# PCB-MicroGPIO.net
KiCad netlist of a schematic drawn in EAGLE
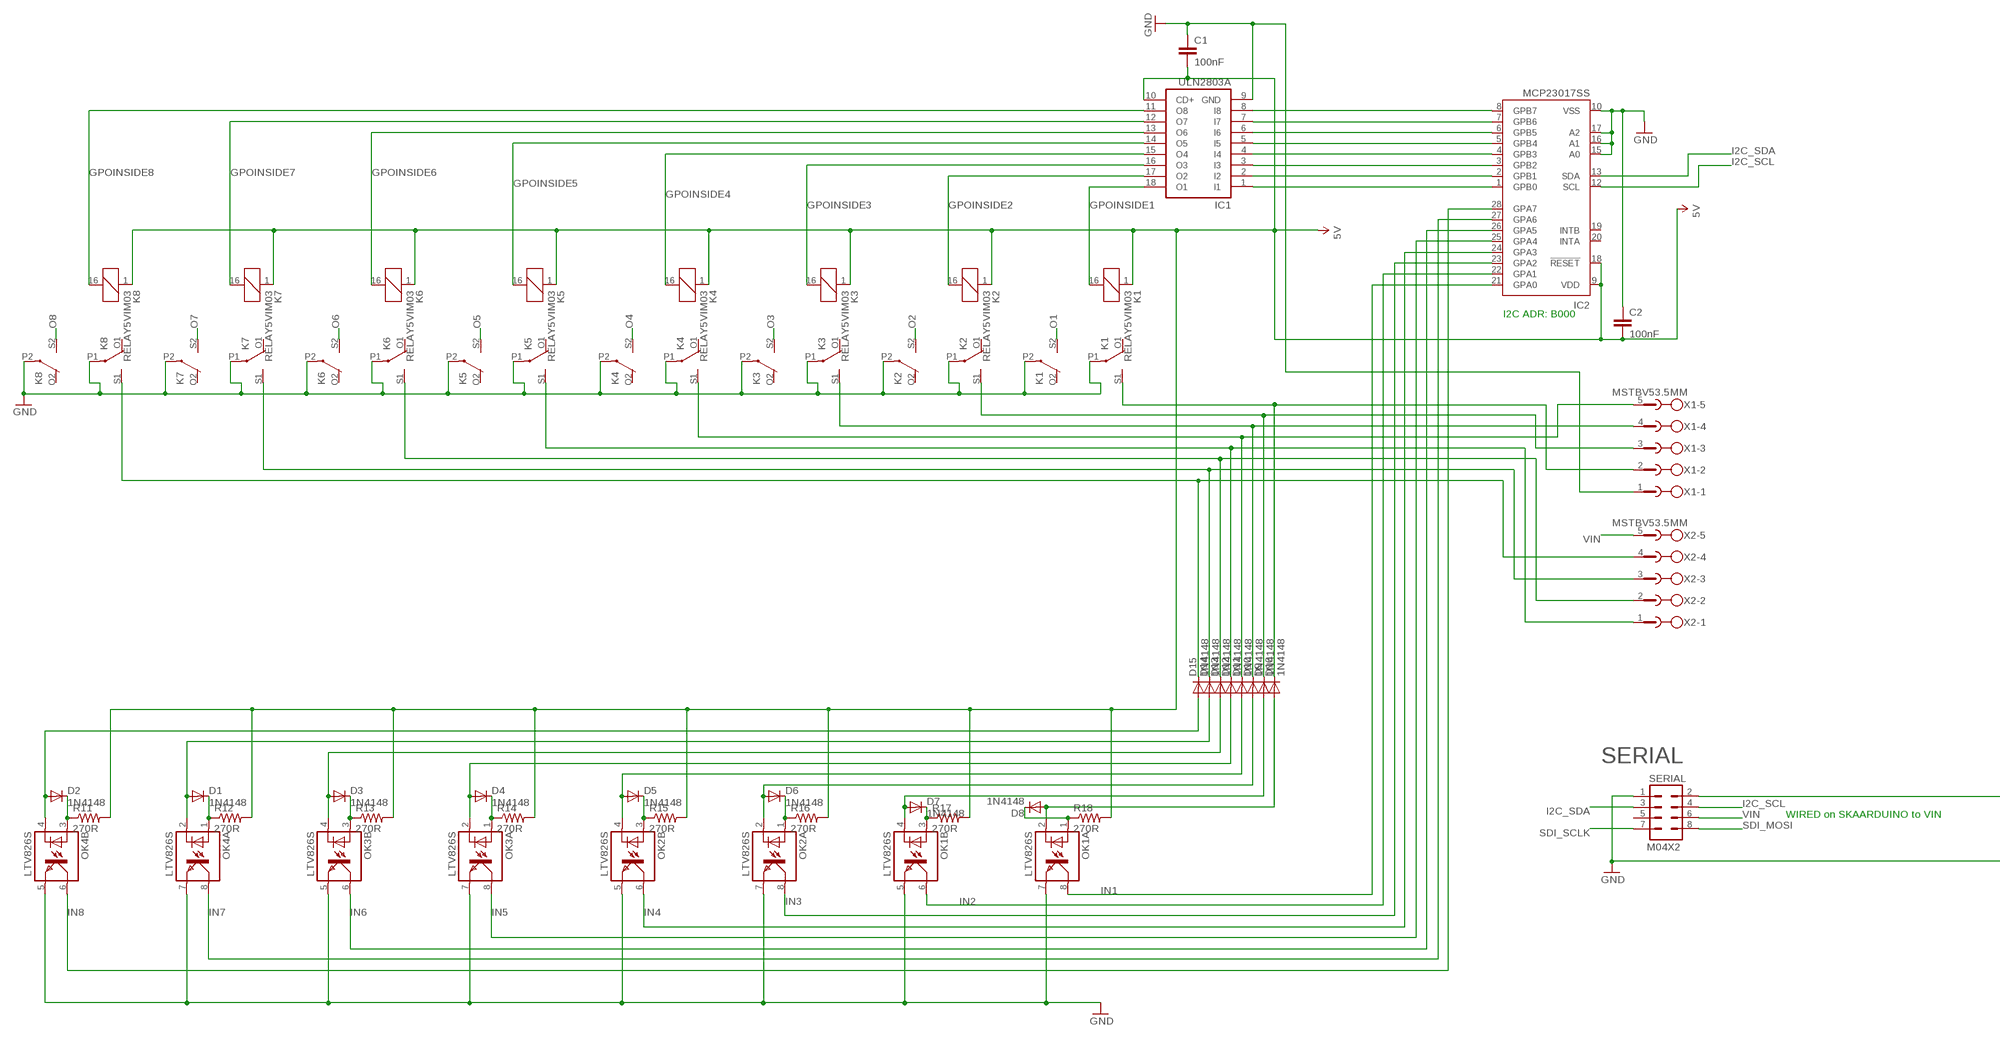
[diagram p0: schematic, sheet 1, part 1 of 2]
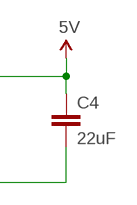
[diagram p1: schematic, sheet 1, part 2 of 2]

(export (version "E")
  (design (tool "Eeschema 10.0.6"))
  (components
    (comp (ref "C1")
      (value "100nF")
      (footprint "eagle-import:0603-CAP")
      (libsource (lib "eagle-import") (part "CAP0603-CAP"))
    )
    (comp (ref "C2")
      (value "100nF")
      (footprint "eagle-import:0603-CAP")
      (libsource (lib "eagle-import") (part "CAP0603-CAP"))
    )
    (comp (ref "C4")
      (value "22uF")
      (footprint "eagle-import:0805")
      (libsource (lib "eagle-import") (part "CAP0805"))
    )
    (comp (ref "D1")
      (value "1N4148")
      (footprint "eagle-import:SOD-323")
      (libsource (lib "eagle-import") (part "DIODESOD"))
    )
    (comp (ref "D2")
      (value "1N4148")
      (footprint "eagle-import:SOD-323")
      (libsource (lib "eagle-import") (part "DIODESOD"))
    )
    (comp (ref "D3")
      (value "1N4148")
      (footprint "eagle-import:SOD-323")
      (libsource (lib "eagle-import") (part "DIODESOD"))
    )
    (comp (ref "D4")
      (value "1N4148")
      (footprint "eagle-import:SOD-323")
      (libsource (lib "eagle-import") (part "DIODESOD"))
    )
    (comp (ref "D5")
      (value "1N4148")
      (footprint "eagle-import:SOD-323")
      (libsource (lib "eagle-import") (part "DIODESOD"))
    )
    (comp (ref "D6")
      (value "1N4148")
      (footprint "eagle-import:SOD-323")
      (libsource (lib "eagle-import") (part "DIODESOD"))
    )
    (comp (ref "D7")
      (value "1N4148")
      (footprint "eagle-import:SOD-323")
      (libsource (lib "eagle-import") (part "DIODESOD"))
    )
    (comp (ref "D8")
      (value "1N4148")
      (footprint "eagle-import:SOD-323")
      (libsource (lib "eagle-import") (part "DIODESOD"))
    )
    (comp (ref "D9")
      (value "1N4148")
      (footprint "eagle-import:SOD-323")
      (libsource (lib "eagle-import") (part "DIODESOD"))
    )
    (comp (ref "D10")
      (value "1N4148")
      (footprint "eagle-import:SOD-323")
      (libsource (lib "eagle-import") (part "DIODESOD"))
    )
    (comp (ref "D11")
      (value "1N4148")
      (footprint "eagle-import:SOD-323")
      (libsource (lib "eagle-import") (part "DIODESOD"))
    )
    (comp (ref "D12")
      (value "1N4148")
      (footprint "eagle-import:SOD-323")
      (libsource (lib "eagle-import") (part "DIODESOD"))
    )
    (comp (ref "D13")
      (value "1N4148")
      (footprint "eagle-import:SOD-323")
      (libsource (lib "eagle-import") (part "DIODESOD"))
    )
    (comp (ref "D14")
      (value "1N4148")
      (footprint "eagle-import:SOD-323")
      (libsource (lib "eagle-import") (part "DIODESOD"))
    )
    (comp (ref "D15")
      (value "1N4148")
      (footprint "eagle-import:SOD-323")
      (libsource (lib "eagle-import") (part "DIODESOD"))
    )
    (comp (ref "D16")
      (value "1N4148")
      (footprint "eagle-import:SOD-323")
      (libsource (lib "eagle-import") (part "DIODESOD"))
    )
    (comp (ref "IC1")
      (value "ULN2803A")
      (footprint "eagle-import:SO18W")
      (libsource (lib "eagle-import") (part "ULN2803ASO18W"))
    )
    (comp (ref "IC2")
      (value "MCP23017SS")
      (footprint "eagle-import:SSOP28")
      (fields (field (name "MF") "MICROCHIP") (field (name "MPN") "MCP23017-E/SS"))
      (libsource (lib "eagle-import") (part "MCP23017SS"))
    )
    (comp (ref "K1")
      (value "RELAY5VIM03")
      (footprint "eagle-import:DS2Y")
      (libsource (lib "eagle-import") (part "RELAY5VIM03"))
    )
    (comp (ref "K2")
      (value "RELAY5VIM03")
      (footprint "eagle-import:DS2Y")
      (libsource (lib "eagle-import") (part "RELAY5VIM03"))
    )
    (comp (ref "K3")
      (value "RELAY5VIM03")
      (footprint "eagle-import:DS2Y")
      (libsource (lib "eagle-import") (part "RELAY5VIM03"))
    )
    (comp (ref "K4")
      (value "RELAY5VIM03")
      (footprint "eagle-import:DS2Y")
      (libsource (lib "eagle-import") (part "RELAY5VIM03"))
    )
    (comp (ref "K5")
      (value "RELAY5VIM03")
      (footprint "eagle-import:DS2Y")
      (libsource (lib "eagle-import") (part "RELAY5VIM03"))
    )
    (comp (ref "K6")
      (value "RELAY5VIM03")
      (footprint "eagle-import:DS2Y")
      (libsource (lib "eagle-import") (part "RELAY5VIM03"))
    )
    (comp (ref "K7")
      (value "RELAY5VIM03")
      (footprint "eagle-import:DS2Y")
      (libsource (lib "eagle-import") (part "RELAY5VIM03"))
    )
    (comp (ref "K8")
      (value "RELAY5VIM03")
      (footprint "eagle-import:DS2Y")
      (libsource (lib "eagle-import") (part "RELAY5VIM03"))
    )
    (comp (ref "OK1")
      (value "LTV826S")
      (footprint "eagle-import:DIL8-SMD")
      (libsource (lib "eagle-import") (part "LTV826S"))
    )
    (comp (ref "OK2")
      (value "LTV826S")
      (footprint "eagle-import:DIL8-SMD")
      (libsource (lib "eagle-import") (part "LTV826S"))
    )
    (comp (ref "OK3")
      (value "LTV826S")
      (footprint "eagle-import:DIL8-SMD")
      (libsource (lib "eagle-import") (part "LTV826S"))
    )
    (comp (ref "OK4")
      (value "LTV826S")
      (footprint "eagle-import:DIL8-SMD")
      (libsource (lib "eagle-import") (part "LTV826S"))
    )
    (comp (ref "R11")
      (value "270R")
      (footprint "eagle-import:0603-RES")
      (libsource (lib "eagle-import") (part "RESISTOR0603-RES"))
    )
    (comp (ref "R12")
      (value "270R")
      (footprint "eagle-import:0603-RES")
      (libsource (lib "eagle-import") (part "RESISTOR0603-RES"))
    )
    (comp (ref "R13")
      (value "270R")
      (footprint "eagle-import:0603-RES")
      (libsource (lib "eagle-import") (part "RESISTOR0603-RES"))
    )
    (comp (ref "R14")
      (value "270R")
      (footprint "eagle-import:0603-RES")
      (libsource (lib "eagle-import") (part "RESISTOR0603-RES"))
    )
    (comp (ref "R15")
      (value "270R")
      (footprint "eagle-import:0603-RES")
      (libsource (lib "eagle-import") (part "RESISTOR0603-RES"))
    )
    (comp (ref "R16")
      (value "270R")
      (footprint "eagle-import:0603-RES")
      (libsource (lib "eagle-import") (part "RESISTOR0603-RES"))
    )
    (comp (ref "R17")
      (value "270R")
      (footprint "eagle-import:0603-RES")
      (libsource (lib "eagle-import") (part "RESISTOR0603-RES"))
    )
    (comp (ref "R18")
      (value "270R")
      (footprint "eagle-import:0603-RES")
      (libsource (lib "eagle-import") (part "RESISTOR0603-RES"))
    )
    (comp (ref "SERIAL")
      (value "M04X2")
      (footprint "eagle-import:2X4")
      (libsource (lib "eagle-import") (part "M04X2"))
    )
    (comp (ref "X1")
      (value "MSTBV53.5MM")
      (footprint "eagle-import:MSTBV5-3.5")
      (libsource (lib "eagle-import") (part "MSTBV53.5MM"))
    )
    (comp (ref "X2")
      (value "MSTBV53.5MM")
      (footprint "eagle-import:MSTBV5-3.5")
      (libsource (lib "eagle-import") (part "MSTBV53.5MM"))
    )
  )
  (nets
    (net (code "1") (name "5V") (class "Default")
      (node (ref "C1") (pin "2") (pinfunction "2_2") (pintype "passive"))
      (node (ref "C2") (pin "2") (pinfunction "2_2") (pintype "passive"))
      (node (ref "C4") (pin "1") (pinfunction "1_1") (pintype "passive"))
      (node (ref "IC1") (pin "10") (pinfunction "CD+_10") (pintype "passive"))
      (node (ref "IC2") (pin "18") (pinfunction "~{RESET}_18") (pintype "input"))
      (node (ref "IC2") (pin "9") (pinfunction "VDD_9") (pintype "power_in"))
      (node (ref "K1") (pin "1") (pinfunction "1_1") (pintype "passive"))
      (node (ref "K2") (pin "1") (pinfunction "1_1") (pintype "passive"))
      (node (ref "K3") (pin "1") (pinfunction "1_1") (pintype "passive"))
      (node (ref "K4") (pin "1") (pinfunction "1_1") (pintype "passive"))
      (node (ref "K5") (pin "1") (pinfunction "1_1") (pintype "passive"))
      (node (ref "K6") (pin "1") (pinfunction "1_1") (pintype "passive"))
      (node (ref "K7") (pin "1") (pinfunction "1_1") (pintype "passive"))
      (node (ref "K8") (pin "1") (pinfunction "1_1") (pintype "passive"))
      (node (ref "R11") (pin "2") (pinfunction "2_2") (pintype "passive"))
      (node (ref "R12") (pin "2") (pinfunction "2_2") (pintype "passive"))
      (node (ref "R13") (pin "2") (pinfunction "2_2") (pintype "passive"))
      (node (ref "R14") (pin "2") (pinfunction "2_2") (pintype "passive"))
      (node (ref "R15") (pin "2") (pinfunction "2_2") (pintype "passive"))
      (node (ref "R16") (pin "2") (pinfunction "2_2") (pintype "passive"))
      (node (ref "R17") (pin "2") (pinfunction "2_2") (pintype "passive"))
      (node (ref "R18") (pin "2") (pinfunction "2_2") (pintype "passive"))
      (node (ref "SERIAL") (pin "2") (pinfunction "2_2") (pintype "passive"))
    )
    (net (code "2") (name "GND") (class "Default")
      (node (ref "C1") (pin "1") (pinfunction "1_1") (pintype "passive"))
      (node (ref "C2") (pin "1") (pinfunction "1_1") (pintype "passive"))
      (node (ref "C4") (pin "2") (pinfunction "2_2") (pintype "passive"))
      (node (ref "IC1") (pin "9") (pinfunction "GND_9") (pintype "power_in"))
      (node (ref "IC2") (pin "10") (pinfunction "VSS_10") (pintype "power_in"))
      (node (ref "IC2") (pin "15") (pinfunction "A0_15") (pintype "input"))
      (node (ref "IC2") (pin "16") (pinfunction "A1_16") (pintype "input"))
      (node (ref "IC2") (pin "17") (pinfunction "A2_17") (pintype "input"))
      (node (ref "K1") (pin "P1") (pinfunction "P_P1") (pintype "passive"))
      (node (ref "K1") (pin "P2") (pinfunction "P_P2") (pintype "passive"))
      (node (ref "K2") (pin "P1") (pinfunction "P_P1") (pintype "passive"))
      (node (ref "K2") (pin "P2") (pinfunction "P_P2") (pintype "passive"))
      (node (ref "K3") (pin "P1") (pinfunction "P_P1") (pintype "passive"))
      (node (ref "K3") (pin "P2") (pinfunction "P_P2") (pintype "passive"))
      (node (ref "K4") (pin "P1") (pinfunction "P_P1") (pintype "passive"))
      (node (ref "K4") (pin "P2") (pinfunction "P_P2") (pintype "passive"))
      (node (ref "K5") (pin "P1") (pinfunction "P_P1") (pintype "passive"))
      (node (ref "K5") (pin "P2") (pinfunction "P_P2") (pintype "passive"))
      (node (ref "K6") (pin "P1") (pinfunction "P_P1") (pintype "passive"))
      (node (ref "K6") (pin "P2") (pinfunction "P_P2") (pintype "passive"))
      (node (ref "K7") (pin "P1") (pinfunction "P_P1") (pintype "passive"))
      (node (ref "K7") (pin "P2") (pinfunction "P_P2") (pintype "passive"))
      (node (ref "K8") (pin "P1") (pinfunction "P_P1") (pintype "passive"))
      (node (ref "K8") (pin "P2") (pinfunction "P_P2") (pintype "passive"))
      (node (ref "OK1") (pin "5") (pinfunction "EMIT_5") (pintype "passive"))
      (node (ref "OK1") (pin "7") (pinfunction "EMIT_7") (pintype "passive"))
      (node (ref "OK2") (pin "5") (pinfunction "EMIT_5") (pintype "passive"))
      (node (ref "OK2") (pin "7") (pinfunction "EMIT_7") (pintype "passive"))
      (node (ref "OK3") (pin "5") (pinfunction "EMIT_5") (pintype "passive"))
      (node (ref "OK3") (pin "7") (pinfunction "EMIT_7") (pintype "passive"))
      (node (ref "OK4") (pin "5") (pinfunction "EMIT_5") (pintype "passive"))
      (node (ref "OK4") (pin "7") (pinfunction "EMIT_7") (pintype "passive"))
      (node (ref "SERIAL") (pin "1") (pinfunction "1_1") (pintype "passive"))
      (node (ref "X1") (pin "1") (pinfunction "1_1") (pintype "passive"))
    )
    (net (code "3") (name "GPOINSIDE1") (class "Default")
      (node (ref "IC1") (pin "18") (pinfunction "O1_18") (pintype "open_collector"))
      (node (ref "K1") (pin "16") (pinfunction "2_16") (pintype "passive"))
    )
    (net (code "4") (name "GPOINSIDE2") (class "Default")
      (node (ref "IC1") (pin "17") (pinfunction "O2_17") (pintype "open_collector"))
      (node (ref "K2") (pin "16") (pinfunction "2_16") (pintype "passive"))
    )
    (net (code "5") (name "GPOINSIDE3") (class "Default")
      (node (ref "IC1") (pin "16") (pinfunction "O3_16") (pintype "open_collector"))
      (node (ref "K3") (pin "16") (pinfunction "2_16") (pintype "passive"))
    )
    (net (code "6") (name "GPOINSIDE4") (class "Default")
      (node (ref "IC1") (pin "15") (pinfunction "O4_15") (pintype "open_collector"))
      (node (ref "K4") (pin "16") (pinfunction "2_16") (pintype "passive"))
    )
    (net (code "7") (name "GPOINSIDE5") (class "Default")
      (node (ref "IC1") (pin "14") (pinfunction "O5_14") (pintype "open_collector"))
      (node (ref "K5") (pin "16") (pinfunction "2_16") (pintype "passive"))
    )
    (net (code "8") (name "GPOINSIDE6") (class "Default")
      (node (ref "IC1") (pin "13") (pinfunction "O6_13") (pintype "open_collector"))
      (node (ref "K6") (pin "16") (pinfunction "2_16") (pintype "passive"))
    )
    (net (code "9") (name "GPOINSIDE7") (class "Default")
      (node (ref "IC1") (pin "12") (pinfunction "O7_12") (pintype "open_collector"))
      (node (ref "K7") (pin "16") (pinfunction "2_16") (pintype "passive"))
    )
    (net (code "10") (name "GPOINSIDE8") (class "Default")
      (node (ref "IC1") (pin "11") (pinfunction "O8_11") (pintype "open_collector"))
      (node (ref "K8") (pin "16") (pinfunction "2_16") (pintype "passive"))
    )
    (net (code "11") (name "I2C_SCL") (class "Default")
      (node (ref "IC2") (pin "12") (pinfunction "SCL_12") (pintype "input"))
      (node (ref "SERIAL") (pin "4") (pinfunction "4_4") (pintype "passive"))
    )
    (net (code "12") (name "I2C_SDA") (class "Default")
      (node (ref "IC2") (pin "13") (pinfunction "SDA_13") (pintype "bidirectional"))
      (node (ref "SERIAL") (pin "3") (pinfunction "3_3") (pintype "passive"))
    )
    (net (code "13") (name "IN1") (class "Default")
      (node (ref "IC2") (pin "21") (pinfunction "GPA0_21") (pintype "bidirectional"))
      (node (ref "OK1") (pin "8") (pinfunction "COL_8") (pintype "passive"))
    )
    (net (code "14") (name "IN2") (class "Default")
      (node (ref "IC2") (pin "22") (pinfunction "GPA1_22") (pintype "bidirectional"))
      (node (ref "OK1") (pin "6") (pinfunction "COL_6") (pintype "passive"))
    )
    (net (code "15") (name "IN3") (class "Default")
      (node (ref "IC2") (pin "23") (pinfunction "GPA2_23") (pintype "bidirectional"))
      (node (ref "OK2") (pin "8") (pinfunction "COL_8") (pintype "passive"))
    )
    (net (code "16") (name "IN4") (class "Default")
      (node (ref "IC2") (pin "24") (pinfunction "GPA3_24") (pintype "bidirectional"))
      (node (ref "OK2") (pin "6") (pinfunction "COL_6") (pintype "passive"))
    )
    (net (code "17") (name "IN5") (class "Default")
      (node (ref "IC2") (pin "25") (pinfunction "GPA4_25") (pintype "bidirectional"))
      (node (ref "OK3") (pin "8") (pinfunction "COL_8") (pintype "passive"))
    )
    (net (code "18") (name "IN6") (class "Default")
      (node (ref "IC2") (pin "26") (pinfunction "GPA5_26") (pintype "bidirectional"))
      (node (ref "OK3") (pin "6") (pinfunction "COL_6") (pintype "passive"))
    )
    (net (code "19") (name "IN7") (class "Default")
      (node (ref "IC2") (pin "27") (pinfunction "GPA6_27") (pintype "bidirectional"))
      (node (ref "OK4") (pin "8") (pinfunction "COL_8") (pintype "passive"))
    )
    (net (code "20") (name "IN8") (class "Default")
      (node (ref "IC2") (pin "28") (pinfunction "GPA7_28") (pintype "bidirectional"))
      (node (ref "OK4") (pin "6") (pinfunction "COL_6") (pintype "passive"))
    )
    (net (code "21") (name "Net-(D1-A)") (class "Default")
      (node (ref "D1") (pin "2") (pinfunction "A_2") (pintype "passive"))
      (node (ref "D14") (pin "2") (pinfunction "A_2") (pintype "passive"))
      (node (ref "OK4") (pin "2") (pinfunction "C_2") (pintype "passive"))
    )
    (net (code "22") (name "Net-(D1-C)") (class "Default")
      (node (ref "D1") (pin "1") (pinfunction "C_1") (pintype "passive"))
      (node (ref "OK4") (pin "1") (pinfunction "A_1") (pintype "passive"))
      (node (ref "R12") (pin "1") (pinfunction "1_1") (pintype "passive"))
    )
    (net (code "23") (name "Net-(D2-C)") (class "Default")
      (node (ref "D2") (pin "1") (pinfunction "C_1") (pintype "passive"))
      (node (ref "OK4") (pin "3") (pinfunction "A_3") (pintype "passive"))
      (node (ref "R11") (pin "1") (pinfunction "1_1") (pintype "passive"))
    )
    (net (code "24") (name "Net-(D3-C)") (class "Default")
      (node (ref "D3") (pin "1") (pinfunction "C_1") (pintype "passive"))
      (node (ref "OK3") (pin "3") (pinfunction "A_3") (pintype "passive"))
      (node (ref "R13") (pin "1") (pinfunction "1_1") (pintype "passive"))
    )
    (net (code "25") (name "Net-(D4-C)") (class "Default")
      (node (ref "D4") (pin "1") (pinfunction "C_1") (pintype "passive"))
      (node (ref "OK3") (pin "1") (pinfunction "A_1") (pintype "passive"))
      (node (ref "R14") (pin "1") (pinfunction "1_1") (pintype "passive"))
    )
    (net (code "26") (name "Net-(D5-C)") (class "Default")
      (node (ref "D5") (pin "1") (pinfunction "C_1") (pintype "passive"))
      (node (ref "OK2") (pin "3") (pinfunction "A_3") (pintype "passive"))
      (node (ref "R15") (pin "1") (pinfunction "1_1") (pintype "passive"))
    )
    (net (code "27") (name "Net-(D6-C)") (class "Default")
      (node (ref "D6") (pin "1") (pinfunction "C_1") (pintype "passive"))
      (node (ref "OK2") (pin "1") (pinfunction "A_1") (pintype "passive"))
      (node (ref "R16") (pin "1") (pinfunction "1_1") (pintype "passive"))
    )
    (net (code "28") (name "Net-(D7-A)") (class "Default")
      (node (ref "D7") (pin "2") (pinfunction "A_2") (pintype "passive"))
      (node (ref "D9") (pin "2") (pinfunction "A_2") (pintype "passive"))
      (node (ref "OK1") (pin "4") (pinfunction "C_4") (pintype "passive"))
    )
    (net (code "29") (name "Net-(D7-C)") (class "Default")
      (node (ref "D7") (pin "1") (pinfunction "C_1") (pintype "passive"))
      (node (ref "OK1") (pin "3") (pinfunction "A_3") (pintype "passive"))
      (node (ref "R17") (pin "1") (pinfunction "1_1") (pintype "passive"))
    )
    (net (code "30") (name "Net-(D8-C)") (class "Default")
      (node (ref "D8") (pin "1") (pinfunction "C_1") (pintype "passive"))
      (node (ref "OK1") (pin "1") (pinfunction "A_1") (pintype "passive"))
      (node (ref "R18") (pin "1") (pinfunction "1_1") (pintype "passive"))
    )
    (net (code "31") (name "Net-(D9-C)") (class "Default")
      (node (ref "D9") (pin "1") (pinfunction "C_1") (pintype "passive"))
      (node (ref "K2") (pin "S1") (pinfunction "S_S1") (pintype "passive"))
      (node (ref "X1") (pin "3") (pinfunction "1_3") (pintype "passive"))
    )
    (net (code "32") (name "Net-(D10-A)") (class "Default")
      (node (ref "D10") (pin "2") (pinfunction "A_2") (pintype "passive"))
      (node (ref "D6") (pin "2") (pinfunction "A_2") (pintype "passive"))
      (node (ref "OK2") (pin "2") (pinfunction "C_2") (pintype "passive"))
    )
    (net (code "33") (name "Net-(D10-C)") (class "Default")
      (node (ref "D10") (pin "1") (pinfunction "C_1") (pintype "passive"))
      (node (ref "K3") (pin "S1") (pinfunction "S_S1") (pintype "passive"))
      (node (ref "X1") (pin "4") (pinfunction "1_4") (pintype "passive"))
    )
    (net (code "34") (name "Net-(D11-A)") (class "Default")
      (node (ref "D11") (pin "2") (pinfunction "A_2") (pintype "passive"))
      (node (ref "D5") (pin "2") (pinfunction "A_2") (pintype "passive"))
      (node (ref "OK2") (pin "4") (pinfunction "C_4") (pintype "passive"))
    )
    (net (code "35") (name "Net-(D11-C)") (class "Default")
      (node (ref "D11") (pin "1") (pinfunction "C_1") (pintype "passive"))
      (node (ref "K4") (pin "S1") (pinfunction "S_S1") (pintype "passive"))
      (node (ref "X1") (pin "5") (pinfunction "1_5") (pintype "passive"))
    )
    (net (code "36") (name "Net-(D12-A)") (class "Default")
      (node (ref "D12") (pin "2") (pinfunction "A_2") (pintype "passive"))
      (node (ref "D4") (pin "2") (pinfunction "A_2") (pintype "passive"))
      (node (ref "OK3") (pin "2") (pinfunction "C_2") (pintype "passive"))
    )
    (net (code "37") (name "Net-(D12-C)") (class "Default")
      (node (ref "D12") (pin "1") (pinfunction "C_1") (pintype "passive"))
      (node (ref "K5") (pin "S1") (pinfunction "S_S1") (pintype "passive"))
      (node (ref "X2") (pin "1") (pinfunction "1_1") (pintype "passive"))
    )
    (net (code "38") (name "Net-(D13-A)") (class "Default")
      (node (ref "D13") (pin "2") (pinfunction "A_2") (pintype "passive"))
      (node (ref "D3") (pin "2") (pinfunction "A_2") (pintype "passive"))
      (node (ref "OK3") (pin "4") (pinfunction "C_4") (pintype "passive"))
    )
    (net (code "39") (name "Net-(D13-C)") (class "Default")
      (node (ref "D13") (pin "1") (pinfunction "C_1") (pintype "passive"))
      (node (ref "K6") (pin "S1") (pinfunction "S_S1") (pintype "passive"))
      (node (ref "X2") (pin "2") (pinfunction "1_2") (pintype "passive"))
    )
    (net (code "40") (name "Net-(D14-C)") (class "Default")
      (node (ref "D14") (pin "1") (pinfunction "C_1") (pintype "passive"))
      (node (ref "K7") (pin "S1") (pinfunction "S_S1") (pintype "passive"))
      (node (ref "X2") (pin "3") (pinfunction "1_3") (pintype "passive"))
    )
    (net (code "41") (name "Net-(D15-A)") (class "Default")
      (node (ref "D15") (pin "2") (pinfunction "A_2") (pintype "passive"))
      (node (ref "D2") (pin "2") (pinfunction "A_2") (pintype "passive"))
      (node (ref "OK4") (pin "4") (pinfunction "C_4") (pintype "passive"))
    )
    (net (code "42") (name "Net-(D15-C)") (class "Default")
      (node (ref "D15") (pin "1") (pinfunction "C_1") (pintype "passive"))
      (node (ref "K8") (pin "S1") (pinfunction "S_S1") (pintype "passive"))
      (node (ref "X2") (pin "4") (pinfunction "1_4") (pintype "passive"))
    )
    (net (code "43") (name "Net-(D16-A)") (class "Default")
      (node (ref "D16") (pin "2") (pinfunction "A_2") (pintype "passive"))
      (node (ref "D8") (pin "2") (pinfunction "A_2") (pintype "passive"))
      (node (ref "OK1") (pin "2") (pinfunction "C_2") (pintype "passive"))
    )
    (net (code "44") (name "Net-(D16-C)") (class "Default")
      (node (ref "D16") (pin "1") (pinfunction "C_1") (pintype "passive"))
      (node (ref "K1") (pin "S1") (pinfunction "S_S1") (pintype "passive"))
      (node (ref "X1") (pin "2") (pinfunction "1_2") (pintype "passive"))
    )
    (net (code "45") (name "Net-(IC1-I1)") (class "Default")
      (node (ref "IC1") (pin "1") (pinfunction "I1_1") (pintype "input"))
      (node (ref "IC2") (pin "1") (pinfunction "GPB0_1") (pintype "bidirectional"))
    )
    (net (code "46") (name "Net-(IC1-I2)") (class "Default")
      (node (ref "IC1") (pin "2") (pinfunction "I2_2") (pintype "input"))
      (node (ref "IC2") (pin "2") (pinfunction "GPB1_2") (pintype "bidirectional"))
    )
    (net (code "47") (name "Net-(IC1-I3)") (class "Default")
      (node (ref "IC1") (pin "3") (pinfunction "I3_3") (pintype "input"))
      (node (ref "IC2") (pin "3") (pinfunction "GPB2_3") (pintype "bidirectional"))
    )
    (net (code "48") (name "Net-(IC1-I4)") (class "Default")
      (node (ref "IC1") (pin "4") (pinfunction "I4_4") (pintype "input"))
      (node (ref "IC2") (pin "4") (pinfunction "GPB3_4") (pintype "bidirectional"))
    )
    (net (code "49") (name "Net-(IC1-I5)") (class "Default")
      (node (ref "IC1") (pin "5") (pinfunction "I5_5") (pintype "input"))
      (node (ref "IC2") (pin "5") (pinfunction "GPB4_5") (pintype "bidirectional"))
    )
    (net (code "50") (name "Net-(IC1-I6)") (class "Default")
      (node (ref "IC1") (pin "6") (pinfunction "I6_6") (pintype "input"))
      (node (ref "IC2") (pin "6") (pinfunction "GPB5_6") (pintype "bidirectional"))
    )
    (net (code "51") (name "Net-(IC1-I7)") (class "Default")
      (node (ref "IC1") (pin "7") (pinfunction "I7_7") (pintype "input"))
      (node (ref "IC2") (pin "7") (pinfunction "GPB6_7") (pintype "bidirectional"))
    )
    (net (code "52") (name "Net-(IC1-I8)") (class "Default")
      (node (ref "IC1") (pin "8") (pinfunction "I8_8") (pintype "input"))
      (node (ref "IC2") (pin "8") (pinfunction "GPB7_8") (pintype "bidirectional"))
    )
    (net (code "53") (name "O1") (class "Default")
      (node (ref "K1") (pin "S2") (pinfunction "S_S2") (pintype "passive"))
    )
    (net (code "54") (name "O2") (class "Default")
      (node (ref "K2") (pin "S2") (pinfunction "S_S2") (pintype "passive"))
    )
    (net (code "55") (name "O3") (class "Default")
      (node (ref "K3") (pin "S2") (pinfunction "S_S2") (pintype "passive"))
    )
    (net (code "56") (name "O4") (class "Default")
      (node (ref "K4") (pin "S2") (pinfunction "S_S2") (pintype "passive"))
    )
    (net (code "57") (name "O5") (class "Default")
      (node (ref "K5") (pin "S2") (pinfunction "S_S2") (pintype "passive"))
    )
    (net (code "58") (name "O6") (class "Default")
      (node (ref "K6") (pin "S2") (pinfunction "S_S2") (pintype "passive"))
    )
    (net (code "59") (name "O7") (class "Default")
      (node (ref "K7") (pin "S2") (pinfunction "S_S2") (pintype "passive"))
    )
    (net (code "60") (name "O8") (class "Default")
      (node (ref "K8") (pin "S2") (pinfunction "S_S2") (pintype "passive"))
    )
    (net (code "61") (name "SDI_MOSI") (class "Default")
      (node (ref "SERIAL") (pin "8") (pinfunction "8_8") (pintype "passive"))
    )
    (net (code "62") (name "SDI_SCLK") (class "Default")
      (node (ref "SERIAL") (pin "7") (pinfunction "7_7") (pintype "passive"))
    )
    (net (code "63") (name "VIN") (class "Default")
      (node (ref "SERIAL") (pin "6") (pinfunction "6_6") (pintype "passive"))
      (node (ref "X2") (pin "5") (pinfunction "1_5") (pintype "passive"))
    )
    (net (code "64") (name "unconnected-(IC2-INTA-Pad20)") (class "Default")
      (node (ref "IC2") (pin "20") (pinfunction "INTA_20") (pintype "output"))
    )
    (net (code "65") (name "unconnected-(IC2-INTB-Pad19)") (class "Default")
      (node (ref "IC2") (pin "19") (pinfunction "INTB_19") (pintype "output"))
    )
    (net (code "66") (name "unconnected-(K1B-O-PadO1)") (class "Default")
      (node (ref "K1") (pin "O1") (pinfunction "O_O1") (pintype "passive"))
    )
    (net (code "67") (name "unconnected-(K1C-O-PadO2)") (class "Default")
      (node (ref "K1") (pin "O2") (pinfunction "O_O2") (pintype "passive"))
    )
    (net (code "68") (name "unconnected-(K2B-O-PadO1)") (class "Default")
      (node (ref "K2") (pin "O1") (pinfunction "O_O1") (pintype "passive"))
    )
    (net (code "69") (name "unconnected-(K2C-O-PadO2)") (class "Default")
      (node (ref "K2") (pin "O2") (pinfunction "O_O2") (pintype "passive"))
    )
    (net (code "70") (name "unconnected-(K3B-O-PadO1)") (class "Default")
      (node (ref "K3") (pin "O1") (pinfunction "O_O1") (pintype "passive"))
    )
    (net (code "71") (name "unconnected-(K3C-O-PadO2)") (class "Default")
      (node (ref "K3") (pin "O2") (pinfunction "O_O2") (pintype "passive"))
    )
    (net (code "72") (name "unconnected-(K4B-O-PadO1)") (class "Default")
      (node (ref "K4") (pin "O1") (pinfunction "O_O1") (pintype "passive"))
    )
    (net (code "73") (name "unconnected-(K4C-O-PadO2)") (class "Default")
      (node (ref "K4") (pin "O2") (pinfunction "O_O2") (pintype "passive"))
    )
    (net (code "74") (name "unconnected-(K5B-O-PadO1)") (class "Default")
      (node (ref "K5") (pin "O1") (pinfunction "O_O1") (pintype "passive"))
    )
    (net (code "75") (name "unconnected-(K5C-O-PadO2)") (class "Default")
      (node (ref "K5") (pin "O2") (pinfunction "O_O2") (pintype "passive"))
    )
    (net (code "76") (name "unconnected-(K6B-O-PadO1)") (class "Default")
      (node (ref "K6") (pin "O1") (pinfunction "O_O1") (pintype "passive"))
    )
    (net (code "77") (name "unconnected-(K6C-O-PadO2)") (class "Default")
      (node (ref "K6") (pin "O2") (pinfunction "O_O2") (pintype "passive"))
    )
    (net (code "78") (name "unconnected-(K7B-O-PadO1)") (class "Default")
      (node (ref "K7") (pin "O1") (pinfunction "O_O1") (pintype "passive"))
    )
    (net (code "79") (name "unconnected-(K7C-O-PadO2)") (class "Default")
      (node (ref "K7") (pin "O2") (pinfunction "O_O2") (pintype "passive"))
    )
    (net (code "80") (name "unconnected-(K8B-O-PadO1)") (class "Default")
      (node (ref "K8") (pin "O1") (pinfunction "O_O1") (pintype "passive"))
    )
    (net (code "81") (name "unconnected-(K8C-O-PadO2)") (class "Default")
      (node (ref "K8") (pin "O2") (pinfunction "O_O2") (pintype "passive"))
    )
    (net (code "82") (name "unconnected-(SERIAL-Pad5)") (class "Default")
      (node (ref "SERIAL") (pin "5") (pinfunction "5_5") (pintype "passive"))
    )
  )
)
